# PCB_PUMP.net
KiCad netlist of a schematic drawn in EAGLE
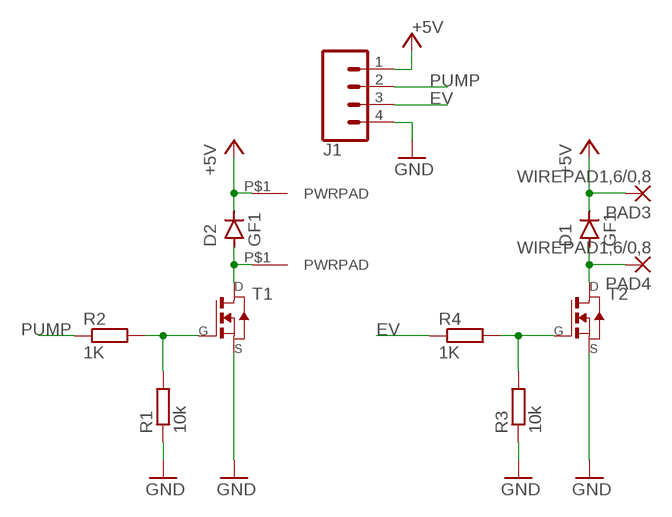
[diagram p0: schematic, sheet 1]

(export (version "E")
  (design (tool "Eeschema 10.0.6"))
  (components
    (comp (ref "D1")
      (value "GF1")
      (footprint "eagle-import:SMA-DO214AC")
      (libsource (lib "eagle-import") (part "GF1"))
    )
    (comp (ref "D2")
      (value "GF1")
      (footprint "eagle-import:SMA-DO214AC")
      (libsource (lib "eagle-import") (part "GF1"))
    )
    (comp (ref "J1")
      (value "CONN_04POLAR")
      (footprint "eagle-import:MOLEX-1X4")
      (libsource (lib "eagle-import") (part "CONN_04POLAR"))
    )
    (comp (ref "J3")
      (value "PWRPAD2-5MM")
      (footprint "eagle-import:PWRPAD_2-5MM")
      (libsource (lib "eagle-import") (part "PWRPAD2-5MM"))
    )
    (comp (ref "J4")
      (value "PWRPAD2-5MM")
      (footprint "eagle-import:PWRPAD_2-5MM")
      (libsource (lib "eagle-import") (part "PWRPAD2-5MM"))
    )
    (comp (ref "PAD3")
      (value "WIREPAD1,6/0,8")
      (footprint "eagle-import:1,6_0,8")
      (libsource (lib "eagle-import") (part "WIREPAD1,6/0,8"))
    )
    (comp (ref "PAD4")
      (value "WIREPAD1,6/0,8")
      (footprint "eagle-import:1,6_0,8")
      (libsource (lib "eagle-import") (part "WIREPAD1,6/0,8"))
    )
    (comp (ref "R1")
      (value "10k")
      (footprint "eagle-import:R1206")
      (libsource (lib "eagle-import") (part "R-EU_R1206"))
    )
    (comp (ref "R2")
      (value "1K")
      (footprint "eagle-import:R1206")
      (libsource (lib "eagle-import") (part "R-EU_R1206"))
    )
    (comp (ref "R3")
      (value "10k")
      (footprint "eagle-import:R1206")
      (libsource (lib "eagle-import") (part "R-EU_R1206"))
    )
    (comp (ref "R4")
      (value "1K")
      (footprint "eagle-import:R1206")
      (libsource (lib "eagle-import") (part "R-EU_R1206"))
    )
    (comp (ref "T1")
      (value "NMOSFETSOT23")
      (footprint "eagle-import:SOT-23")
      (libsource (lib "eagle-import") (part "NMOSFETSOT23"))
    )
    (comp (ref "T2")
      (value "NMOSFETSOT23")
      (footprint "eagle-import:SOT-23")
      (libsource (lib "eagle-import") (part "NMOSFETSOT23"))
    )
  )
  (nets
    (net (code "1") (name "+5V") (class "Default")
      (node (ref "D1") (pin "K") (pinfunction "C_K") (pintype "passive"))
      (node (ref "D2") (pin "K") (pinfunction "C_K") (pintype "passive"))
      (node (ref "J1") (pin "1") (pinfunction "1_1") (pintype "passive"))
      (node (ref "J4") (pin "P$1") (pinfunction "PWRPAD_P$1") (pintype "bidirectional"))
      (node (ref "PAD3") (pin "1") (pinfunction "P_1") (pintype "passive"))
    )
    (net (code "2") (name "/EV") (class "Default")
      (node (ref "J1") (pin "3") (pinfunction "3_3") (pintype "passive"))
      (node (ref "R4") (pin "1") (pinfunction "1_1") (pintype "passive"))
    )
    (net (code "3") (name "/PUMP") (class "Default")
      (node (ref "J1") (pin "2") (pinfunction "2_2") (pintype "passive"))
      (node (ref "R2") (pin "1") (pinfunction "1_1") (pintype "passive"))
    )
    (net (code "4") (name "GND") (class "Default")
      (node (ref "J1") (pin "4") (pinfunction "4_4") (pintype "passive"))
      (node (ref "R1") (pin "1") (pinfunction "1_1") (pintype "passive"))
      (node (ref "R3") (pin "1") (pinfunction "1_1") (pintype "passive"))
      (node (ref "T1") (pin "2") (pinfunction "S_2") (pintype "passive"))
      (node (ref "T2") (pin "2") (pinfunction "S_2") (pintype "passive"))
    )
    (net (code "5") (name "Net-(J3-PWRPAD)") (class "Default")
      (node (ref "D2") (pin "A") (pinfunction "A_A") (pintype "passive"))
      (node (ref "J3") (pin "P$1") (pinfunction "PWRPAD_P$1") (pintype "bidirectional"))
      (node (ref "T1") (pin "1") (pinfunction "D_1") (pintype "passive"))
    )
    (net (code "6") (name "Net-(PAD4-P)") (class "Default")
      (node (ref "D1") (pin "A") (pinfunction "A_A") (pintype "passive"))
      (node (ref "PAD4") (pin "1") (pinfunction "P_1") (pintype "passive"))
      (node (ref "T2") (pin "1") (pinfunction "D_1") (pintype "passive"))
    )
    (net (code "7") (name "Net-(T1-G)") (class "Default")
      (node (ref "R1") (pin "2") (pinfunction "2_2") (pintype "passive"))
      (node (ref "R2") (pin "2") (pinfunction "2_2") (pintype "passive"))
      (node (ref "T1") (pin "3") (pinfunction "G_3") (pintype "passive"))
    )
    (net (code "8") (name "Net-(T2-G)") (class "Default")
      (node (ref "R3") (pin "2") (pinfunction "2_2") (pintype "passive"))
      (node (ref "R4") (pin "2") (pinfunction "2_2") (pintype "passive"))
      (node (ref "T2") (pin "3") (pinfunction "G_3") (pintype "passive"))
    )
  )
)
